# front2ch.net
KiCad netlist of a schematic drawn in Altium Designer
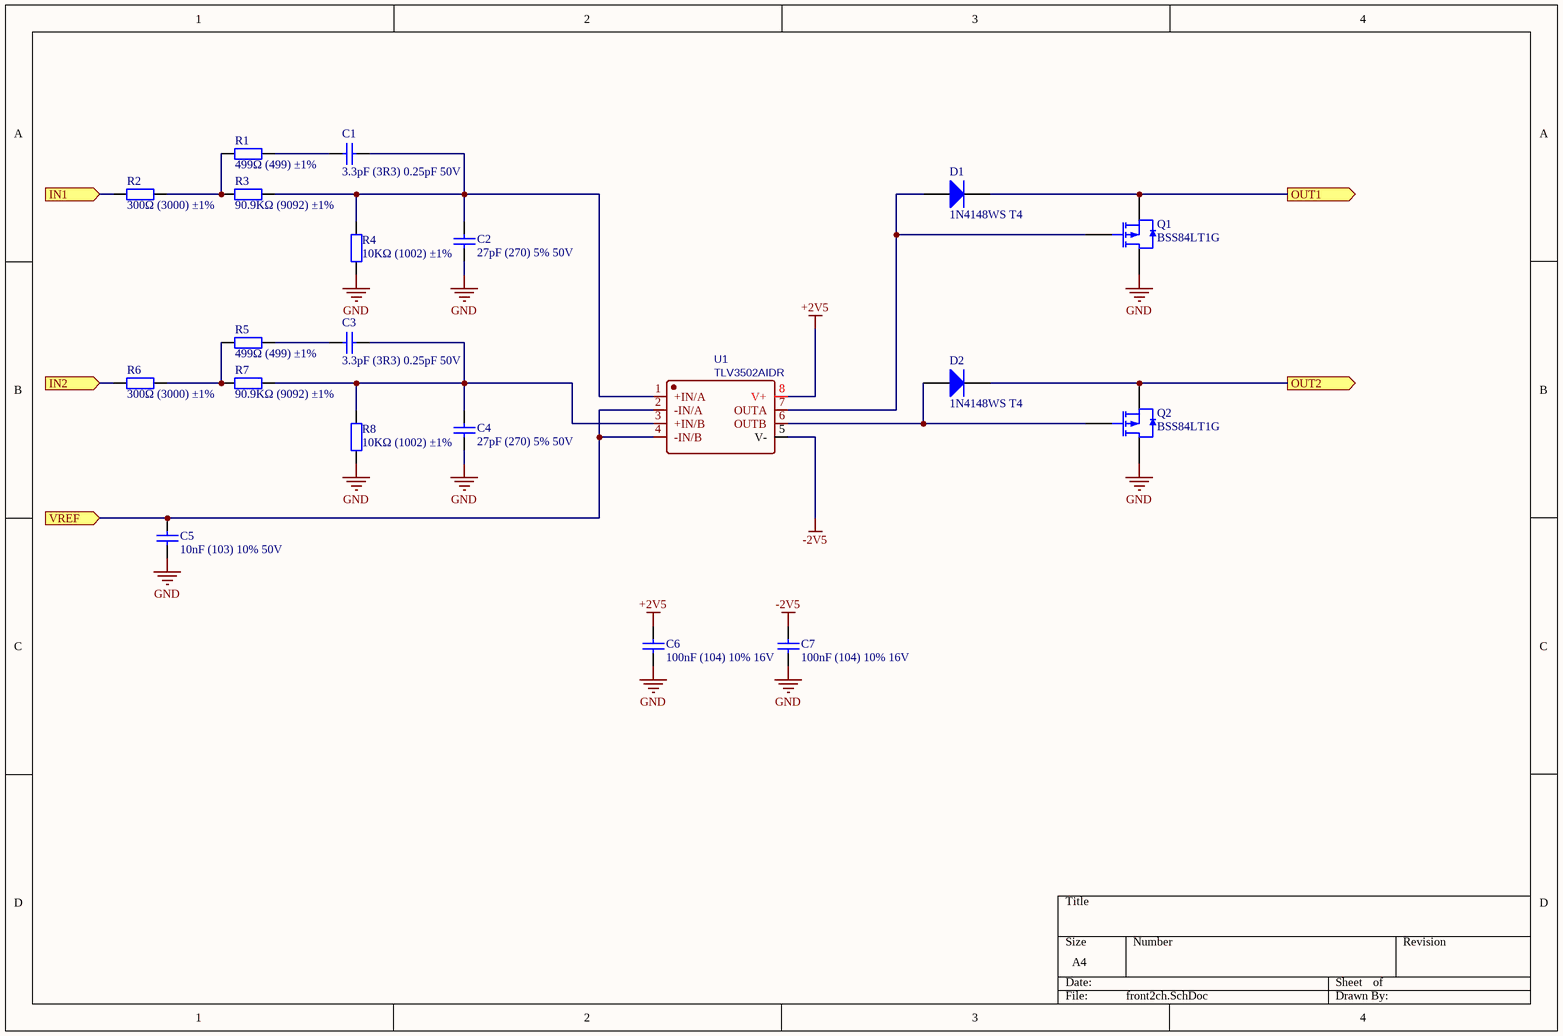
[diagram p0: front2ch.SchDoc]

(export (version "E")
  (design (tool "Eeschema 10.0.6"))
  (components
    (comp (ref "C1")
      (value "3.3pF (3R3) 0.25pF 50V")
      (footprint "0402_C")
      (description "贴片电容")
      (libsource (lib "Miscellaneous Devices LC") (part "0402 3.3pF (3R3) 0.25pF 50V"))
    )
    (comp (ref "C2")
      (value "27pF (270) 5% 50V")
      (footprint "0402_C")
      (description "贴片电容")
      (libsource (lib "Miscellaneous Devices LC") (part "0402 27pF (270) 5% 50V"))
    )
    (comp (ref "C3")
      (value "3.3pF (3R3) 0.25pF 50V")
      (footprint "0402_C")
      (description "贴片电容")
      (libsource (lib "Miscellaneous Devices LC") (part "0402 3.3pF (3R3) 0.25pF 50V"))
    )
    (comp (ref "C4")
      (value "27pF (270) 5% 50V")
      (footprint "0402_C")
      (description "贴片电容")
      (libsource (lib "Miscellaneous Devices LC") (part "0402 27pF (270) 5% 50V"))
    )
    (comp (ref "C5")
      (value "10nF (103) 10% 50V")
      (footprint "0402_C")
      (description "贴片电容")
      (libsource (lib "Miscellaneous Devices LC") (part "0402 10nF (103) 10% 50V"))
    )
    (comp (ref "C6")
      (value "100nF (104) 10% 16V")
      (footprint "0402_C")
      (description "贴片电容")
      (libsource (lib "Miscellaneous Devices LC") (part "0402 100nF (104) 10% 16V"))
    )
    (comp (ref "C7")
      (value "100nF (104) 10% 16V")
      (footprint "0402_C")
      (description "贴片电容")
      (libsource (lib "Miscellaneous Devices LC") (part "0402 100nF (104) 10% 16V"))
    )
    (comp (ref "D1")
      (value "1N4148WS T4")
      (footprint "SOD-323")
      (description "二极管")
      (libsource (lib "Miscellaneous Devices LC") (part "SOD-323 1N4148WS T4"))
    )
    (comp (ref "D2")
      (value "1N4148WS T4")
      (footprint "SOD-323")
      (description "二极管")
      (libsource (lib "Miscellaneous Devices LC") (part "SOD-323 1N4148WS T4"))
    )
    (comp (ref "Q1")
      (value "BSS84LT1G")
      (footprint "SOT-23(SOT-23-3)")
      (description "MOS(场效应管)")
      (libsource (lib "Miscellaneous Devices LC") (part "BSS84LT1G"))
    )
    (comp (ref "Q2")
      (value "BSS84LT1G")
      (footprint "SOT-23(SOT-23-3)")
      (description "MOS(场效应管)")
      (libsource (lib "Miscellaneous Devices LC") (part "BSS84LT1G"))
    )
    (comp (ref "R1")
      (value "499Ω (499) ±1%")
      (footprint "0402_R")
      (description "贴片电阻")
      (libsource (lib "Miscellaneous Devices LC") (part "0402 49.9Ω (49R9) 1%"))
    )
    (comp (ref "R2")
      (value "300Ω (3000) ±1%")
      (footprint "0402_R")
      (description "贴片电阻")
      (libsource (lib "Miscellaneous Devices LC") (part "0402 300Ω (3000) 1%"))
    )
    (comp (ref "R3")
      (value "90.9KΩ (9092) ±1%")
      (footprint "0402_R")
      (description "贴片电阻")
      (libsource (lib "Miscellaneous Devices LC") (part "0402 8.2KΩ (8201) 1%"))
    )
    (comp (ref "R4")
      (value "10KΩ (1002) ±1%")
      (footprint "0402_R")
      (description "贴片电阻")
      (libsource (lib "Miscellaneous Devices LC") (part "0402 10KΩ (1002) 1%"))
    )
    (comp (ref "R5")
      (value "499Ω (499) ±1%")
      (footprint "0402_R")
      (description "贴片电阻")
      (libsource (lib "Miscellaneous Devices LC") (part "0402 49.9Ω (49R9) 1%"))
    )
    (comp (ref "R6")
      (value "300Ω (3000) ±1%")
      (footprint "0402_R")
      (description "贴片电阻")
      (libsource (lib "Miscellaneous Devices LC") (part "0402 300Ω (3000) 1%"))
    )
    (comp (ref "R7")
      (value "90.9KΩ (9092) ±1%")
      (footprint "0402_R")
      (description "贴片电阻")
      (libsource (lib "Miscellaneous Devices LC") (part "0402 8.2KΩ (8201) 1%"))
    )
    (comp (ref "R8")
      (value "10KΩ (1002) ±1%")
      (footprint "0402_R")
      (description "贴片电阻")
      (libsource (lib "Miscellaneous Devices LC") (part "0402 10KΩ (1002) 1%"))
    )
    (comp (ref "U1")
      (value "TLV3502AIDR")
      (footprint "SOIC-8_150mil")
      (fields (field (name "BOM_SUPPLIER PART") "C131165") (field (name "CONTRIBUTOR") "LCSC"))
      (libsource (lib "altium-import") (part "root_0_TLV3502AIDR_"))
    )
  )
  (nets
    (net (code "1") (name "+2V5") (class "Default")
      (node (ref "C6") (pin "2") (pinfunction "2_2") (pintype "passive"))
      (node (ref "U1") (pin "8") (pinfunction "V+_8") (pintype "passive"))
    )
    (net (code "2") (name "-2V5") (class "Default")
      (node (ref "C7") (pin "2") (pinfunction "2_2") (pintype "passive"))
      (node (ref "U1") (pin "5") (pinfunction "V-_5") (pintype "passive"))
    )
    (net (code "3") (name "/IN1") (class "Default")
      (node (ref "R2") (pin "1") (pinfunction "1_1") (pintype "passive"))
    )
    (net (code "4") (name "/IN2") (class "Default")
      (node (ref "R6") (pin "1") (pinfunction "1_1") (pintype "passive"))
    )
    (net (code "5") (name "/OUT1") (class "Default")
      (node (ref "D1") (pin "2") (pinfunction "K_2") (pintype "passive"))
      (node (ref "Q1") (pin "2") (pinfunction "S_2") (pintype "passive"))
    )
    (net (code "6") (name "/OUT2") (class "Default")
      (node (ref "D2") (pin "2") (pinfunction "K_2") (pintype "passive"))
      (node (ref "Q2") (pin "2") (pinfunction "S_2") (pintype "passive"))
    )
    (net (code "7") (name "/VREF") (class "Default")
      (node (ref "C5") (pin "2") (pinfunction "2_2") (pintype "passive"))
      (node (ref "U1") (pin "2") (pinfunction "-IN/A_2") (pintype "passive"))
      (node (ref "U1") (pin "4") (pinfunction "-IN/B_4") (pintype "passive"))
    )
    (net (code "8") (name "GND") (class "Default")
      (node (ref "C2") (pin "1") (pinfunction "1_1") (pintype "passive"))
      (node (ref "C4") (pin "1") (pinfunction "1_1") (pintype "passive"))
      (node (ref "C5") (pin "1") (pinfunction "1_1") (pintype "passive"))
      (node (ref "C6") (pin "1") (pinfunction "1_1") (pintype "passive"))
      (node (ref "C7") (pin "1") (pinfunction "1_1") (pintype "passive"))
      (node (ref "Q1") (pin "3") (pinfunction "D_3") (pintype "passive"))
      (node (ref "Q2") (pin "3") (pinfunction "D_3") (pintype "passive"))
      (node (ref "R4") (pin "1") (pinfunction "1_1") (pintype "passive"))
      (node (ref "R8") (pin "1") (pinfunction "1_1") (pintype "passive"))
    )
    (net (code "9") (name "Net-(C1-Pad1)") (class "Default")
      (node (ref "C1") (pin "1") (pinfunction "1_1") (pintype "passive"))
      (node (ref "R1") (pin "2") (pinfunction "2_2") (pintype "passive"))
    )
    (net (code "10") (name "Net-(C3-Pad1)") (class "Default")
      (node (ref "C3") (pin "1") (pinfunction "1_1") (pintype "passive"))
      (node (ref "R5") (pin "2") (pinfunction "2_2") (pintype "passive"))
    )
    (net (code "11") (name "Net-(D1-A)") (class "Default")
      (node (ref "D1") (pin "1") (pinfunction "A_1") (pintype "passive"))
      (node (ref "Q1") (pin "1") (pinfunction "G_1") (pintype "passive"))
      (node (ref "U1") (pin "7") (pinfunction "OUTA_7") (pintype "passive"))
    )
    (net (code "12") (name "Net-(D2-A)") (class "Default")
      (node (ref "D2") (pin "1") (pinfunction "A_1") (pintype "passive"))
      (node (ref "Q2") (pin "1") (pinfunction "G_1") (pintype "passive"))
      (node (ref "U1") (pin "6") (pinfunction "OUTB_6") (pintype "passive"))
    )
    (net (code "13") (name "Net-(R1-Pad1)") (class "Default")
      (node (ref "R1") (pin "1") (pinfunction "1_1") (pintype "passive"))
      (node (ref "R2") (pin "2") (pinfunction "2_2") (pintype "passive"))
      (node (ref "R3") (pin "1") (pinfunction "1_1") (pintype "passive"))
    )
    (net (code "14") (name "Net-(R5-Pad1)") (class "Default")
      (node (ref "R5") (pin "1") (pinfunction "1_1") (pintype "passive"))
      (node (ref "R6") (pin "2") (pinfunction "2_2") (pintype "passive"))
      (node (ref "R7") (pin "1") (pinfunction "1_1") (pintype "passive"))
    )
    (net (code "15") (name "Net-(U1-+IN{slash}A)") (class "Default")
      (node (ref "C1") (pin "2") (pinfunction "2_2") (pintype "passive"))
      (node (ref "C2") (pin "2") (pinfunction "2_2") (pintype "passive"))
      (node (ref "R3") (pin "2") (pinfunction "2_2") (pintype "passive"))
      (node (ref "R4") (pin "2") (pinfunction "2_2") (pintype "passive"))
      (node (ref "U1") (pin "1") (pinfunction "+IN/A_1") (pintype "passive"))
    )
    (net (code "16") (name "Net-(U1-+IN{slash}B)") (class "Default")
      (node (ref "C3") (pin "2") (pinfunction "2_2") (pintype "passive"))
      (node (ref "C4") (pin "2") (pinfunction "2_2") (pintype "passive"))
      (node (ref "R7") (pin "2") (pinfunction "2_2") (pintype "passive"))
      (node (ref "R8") (pin "2") (pinfunction "2_2") (pintype "passive"))
      (node (ref "U1") (pin "3") (pinfunction "+IN/B_3") (pintype "passive"))
    )
  )
)
